# 3-RF.net
KiCad netlist of a schematic drawn in Altium Designer
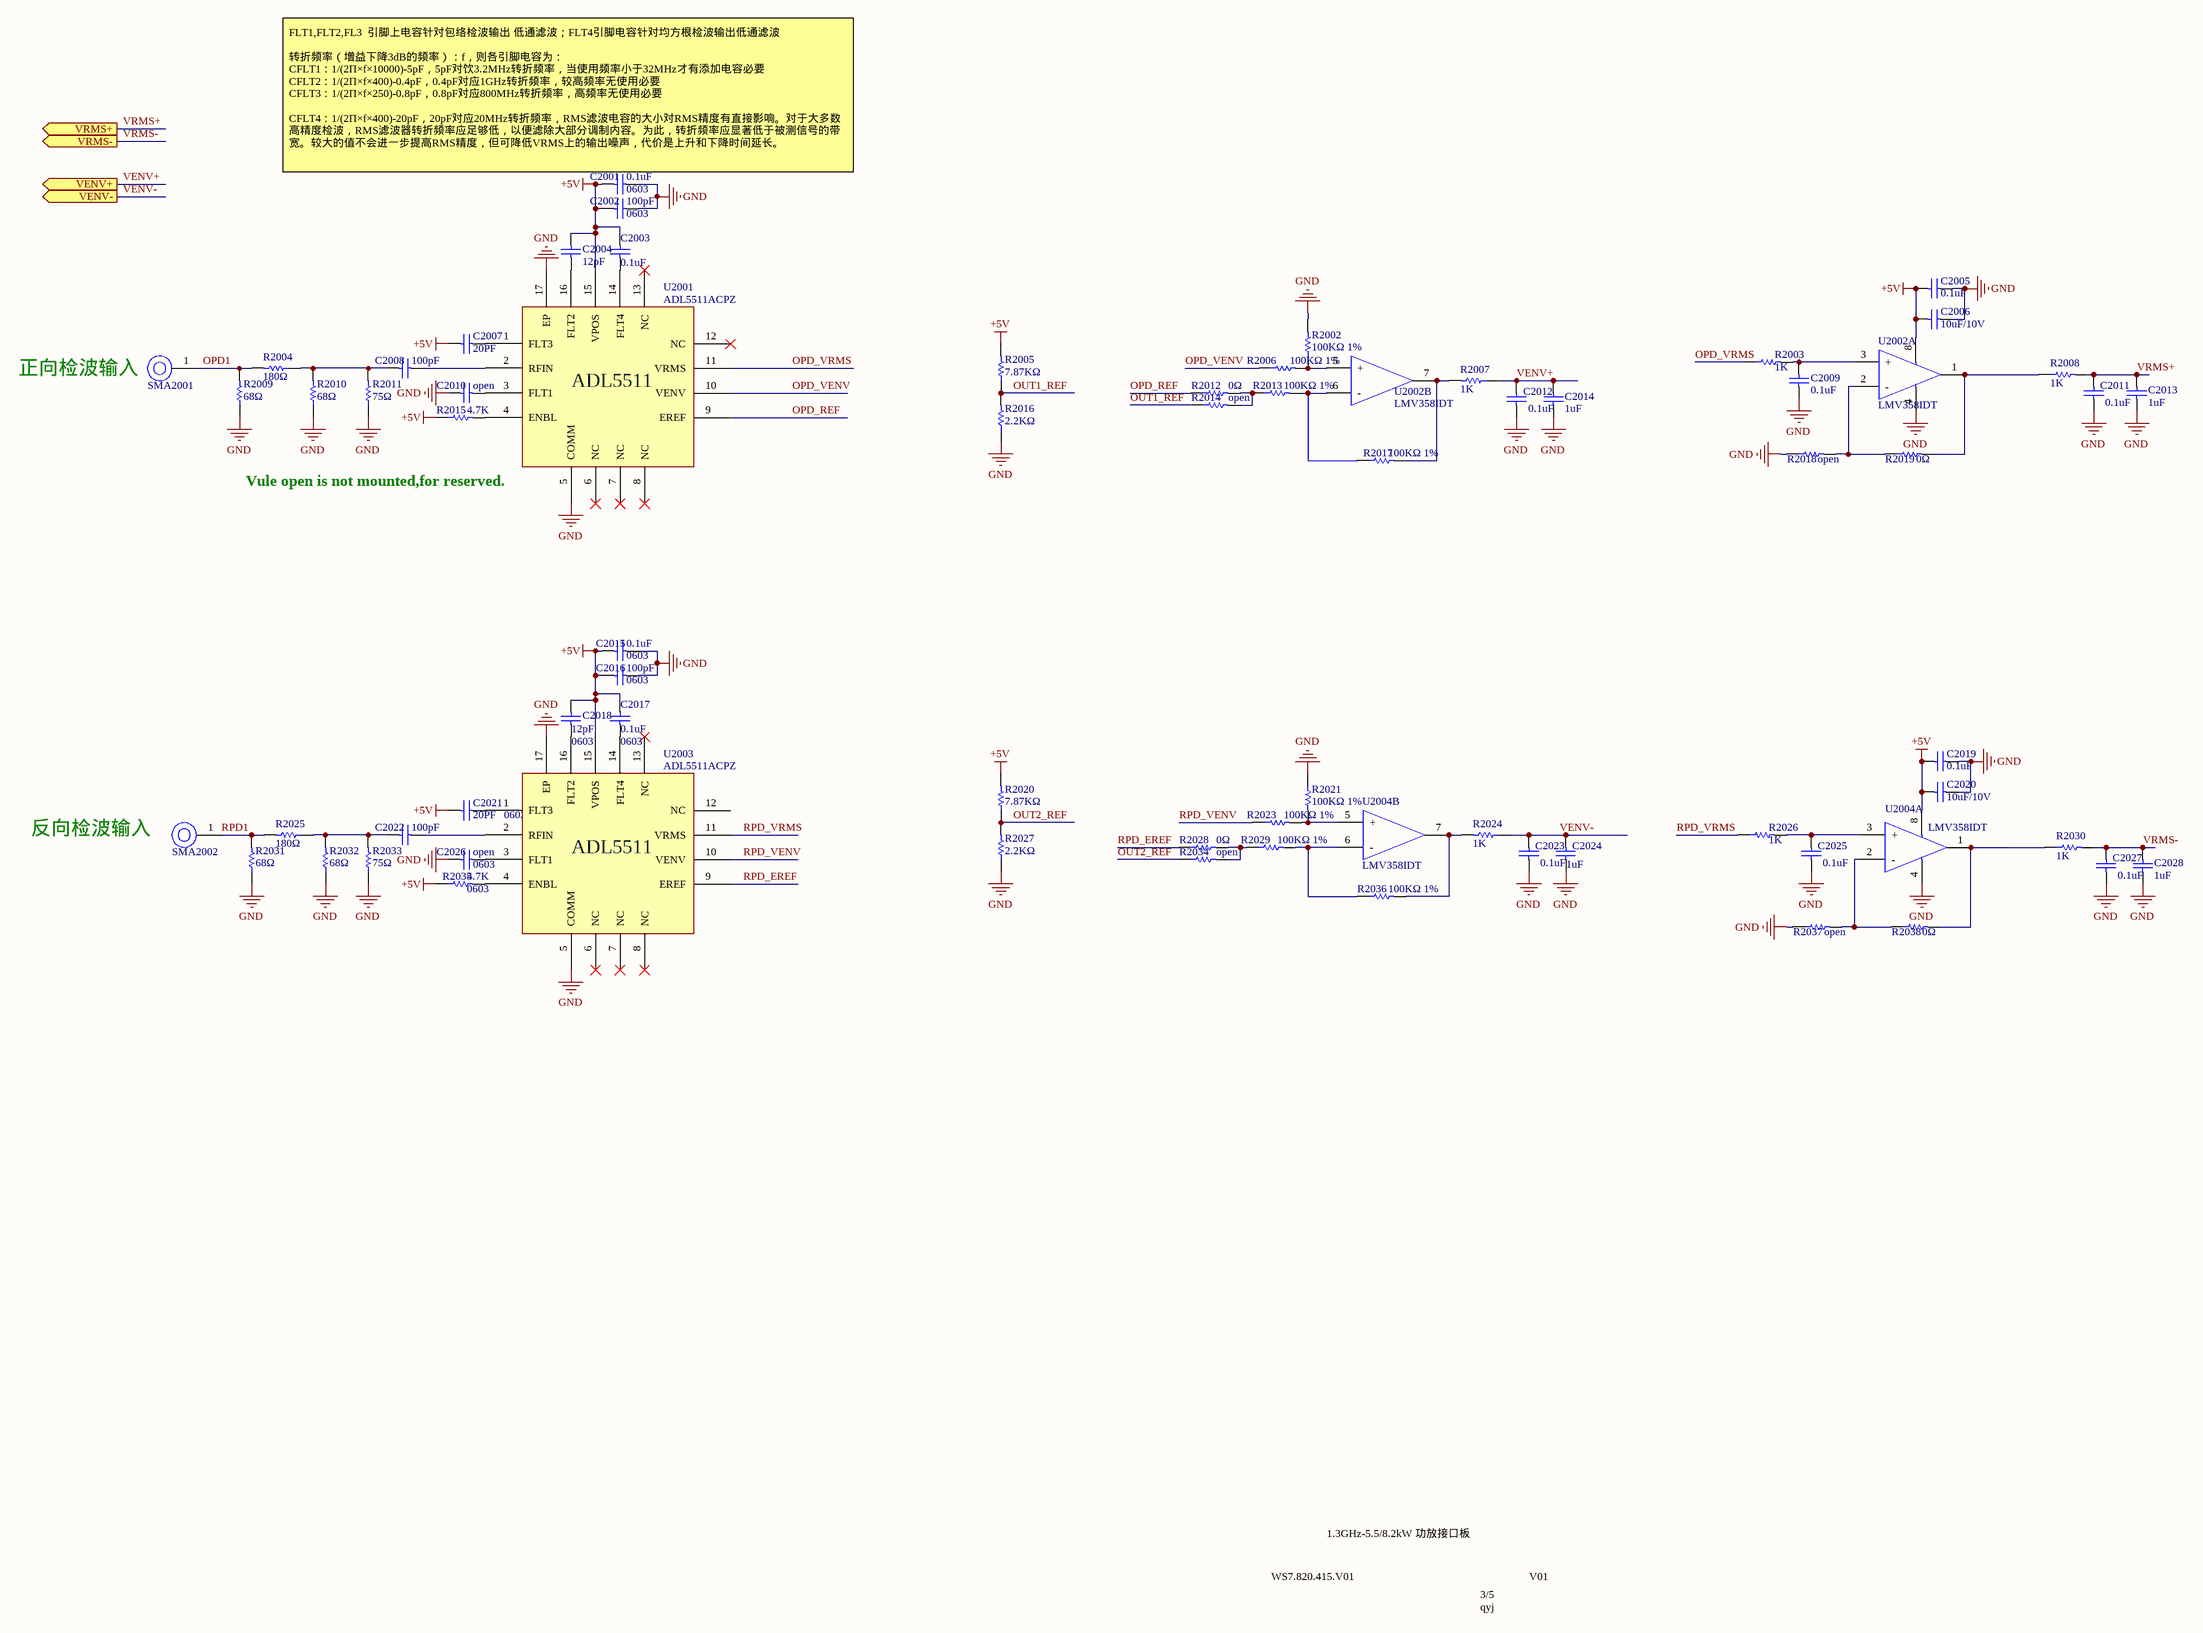
[diagram p0: 3-RF.SchDoc]

(export (version "E")
  (design (tool "Eeschema 10.0.6"))
  (components
    (comp (ref "C2001")
      (value "0.1uF")
      (footprint "C0603")
      (description "贴片电容_GRM188R71H104KA01D_0.1uF±10%,50V,0603")
      (libsource (lib "20贴片电容0603") (part "0.1uF贴片电容"))
    )
    (comp (ref "C2002")
      (value "100pF")
      (footprint "C0603")
      (description "贴片电容_100pF±10%,50V,0603")
      (libsource (lib "20贴片电容0603") (part "1000pF贴片电容"))
    )
    (comp (ref "C2003")
      (value "0.1uF")
      (footprint "C0603")
      (description "贴片电容_GRM188R71H104KA01D_0.1uF±10%,50V,0603")
      (libsource (lib "20贴片电容0603") (part "0.1uF贴片电容"))
    )
    (comp (ref "C2004")
      (value "12pF")
      (footprint "C0603")
      (description "GRM1885C1H390JA01D_39pF±5%,50V,0603")
      (libsource (lib "20贴片电容0603") (part "10pF贴片电容"))
    )
    (comp (ref "C2005")
      (value "0.1uF")
      (footprint "C0603")
      (description "贴片电容_GRM188R71H104KA01D_0.1uF±10%,50V,0603")
      (libsource (lib "20贴片电容0603") (part "0.1uF贴片电容"))
    )
    (comp (ref "C2006")
      (value "10uF/10V")
      (footprint "C0805")
      (description "贴片电容_GRM21BR61A106KE19L_10uF±10%,10V,0805")
      (libsource (lib "21贴片电容0805") (part "10uF贴片电容"))
    )
    (comp (ref "C2007")
      (value "20PF")
      (footprint "C0603")
      (description "贴片电容_GRM1885C1H680JA01D_0603,68PF,50V,±5％,COG")
      (fields (field (name "MPN") "Murata"))
      (libsource (lib "20贴片电容0603") (part "10pF贴片电容"))
    )
    (comp (ref "C2008")
      (value "100pF")
      (footprint "C0805")
      (description "贴片电容_GRM2165C1H101JA01D_100pF±5%,50V,0805")
      (libsource (lib "21贴片电容0805") (part "100pF贴片电容"))
    )
    (comp (ref "C2009")
      (value "0.1uF")
      (footprint "C0603")
      (description "贴片电容_GRM188R71H104KA01D_0.1uF±10%,50V,0603")
      (libsource (lib "20贴片电容0603") (part "0.1uF贴片电容"))
    )
    (comp (ref "C2010")
      (value "open")
      (footprint "C0603")
      (description "贴片电容_GRM188R71H102KA01_1000pF±10%,50V,0603")
      (libsource (lib "20贴片电容0603") (part "1000pF贴片电容"))
    )
    (comp (ref "C2011")
      (value "0.1uF")
      (footprint "C0603")
      (description "贴片电容_GRM188R71H104KA01D_0.1uF±10%,50V,0603")
      (libsource (lib "20贴片电容0603") (part "0.1uF贴片电容"))
    )
    (comp (ref "C2012")
      (value "0.1uF")
      (footprint "C0603")
      (description "贴片电容_GRM188R71H104KA01D_0.1uF±10%,50V,0603")
      (libsource (lib "20贴片电容0603") (part "0.1uF贴片电容"))
    )
    (comp (ref "C2013")
      (value "1uF")
      (footprint "C0603")
      (description "贴片电容_GRM188R60J106ME47D_10uF±20%,6.3V,0603")
      (libsource (lib "20贴片电容0603") (part "10uF贴片电容"))
    )
    (comp (ref "C2014") (value "1uF") (footprint "C0603") (libsource (lib "20贴片电容0603") (part "10uF贴片电容")))
    (comp (ref "C2015")
      (value "0.1uF")
      (footprint "C0603")
      (description "贴片电容_GRM188R71H104KA01D_0.1uF±10%,50V,0603")
      (libsource (lib "20贴片电容0603") (part "0.1uF贴片电容"))
    )
    (comp (ref "C2016")
      (value "100pF")
      (footprint "C0603")
      (description "贴片电容_100pF±10%,50V,0603")
      (libsource (lib "20贴片电容0603") (part "1000pF贴片电容"))
    )
    (comp (ref "C2017")
      (value "0.1uF")
      (footprint "C0603")
      (description "贴片电容_GRM188R71H104KA01D_0.1uF±10%,50V,0603")
      (libsource (lib "20贴片电容0603") (part "0.1uF贴片电容"))
    )
    (comp (ref "C2018")
      (value "12pF")
      (footprint "C0603")
      (description "GRM1885C1H390JA01D_39pF±5%,50V,0603")
      (libsource (lib "20贴片电容0603") (part "10pF贴片电容"))
    )
    (comp (ref "C2019")
      (value "0.1uF")
      (footprint "C0603")
      (description "贴片电容_GRM188R71H104KA01D_0.1uF±10%,50V,0603")
      (libsource (lib "20贴片电容0603") (part "0.1uF贴片电容"))
    )
    (comp (ref "C2020")
      (value "10uF/10V")
      (footprint "C0805")
      (description "贴片电容_GRM21BR61A106KE19L_10uF±10%,10V,0805")
      (libsource (lib "21贴片电容0805") (part "10uF贴片电容"))
    )
    (comp (ref "C2021")
      (value "20PF")
      (footprint "C0603")
      (description "贴片电容_GRM1885C1H680JA01D_0603,68PF,50V,±5％,COG")
      (fields (field (name "MPN") "Murata"))
      (libsource (lib "20贴片电容0603") (part "10pF贴片电容"))
    )
    (comp (ref "C2022")
      (value "100pF")
      (footprint "C0805")
      (description "贴片电容_GRM2165C1H101JA01D_100pF±5%,50V,0805")
      (libsource (lib "21贴片电容0805") (part "100pF贴片电容"))
    )
    (comp (ref "C2023")
      (value "0.1uF")
      (footprint "C0603")
      (description "贴片电容_GRM188R71H104KA01D_0.1uF±10%,50V,0603")
      (libsource (lib "20贴片电容0603") (part "0.1uF贴片电容"))
    )
    (comp (ref "C2024") (value "1uF") (footprint "C0603") (libsource (lib "20贴片电容0603") (part "10uF贴片电容")))
    (comp (ref "C2025")
      (value "0.1uF")
      (footprint "C0603")
      (description "贴片电容_GRM188R71H104KA01D_0.1uF±10%,50V,0603")
      (libsource (lib "20贴片电容0603") (part "0.1uF贴片电容"))
    )
    (comp (ref "C2026")
      (value "open")
      (footprint "C0603")
      (description "贴片电容_GRM188R71H102KA01_1000pF±10%,50V,0603")
      (libsource (lib "20贴片电容0603") (part "1000pF贴片电容"))
    )
    (comp (ref "C2027")
      (value "0.1uF")
      (footprint "C0603")
      (description "贴片电容_GRM188R71H104KA01D_0.1uF±10%,50V,0603")
      (libsource (lib "20贴片电容0603") (part "0.1uF贴片电容"))
    )
    (comp (ref "C2028")
      (value "1uF")
      (footprint "C0603")
      (description "贴片电容_GRM188R60J106ME47D_10uF±20%,6.3V,0603")
      (libsource (lib "20贴片电容0603") (part "10uF贴片电容"))
    )
    (comp (ref "R2002")
      (value "100KΩ 1%")
      (footprint "R0603")
      (libsource (lib "10贴片电阻0603") (part "430Ω贴片电阻"))
    )
    (comp (ref "R2003")
      (value "1K")
      (footprint "R0603")
      (description "贴片电阻_1K±5%,0603")
      (libsource (lib "10贴片电阻0603") (part "1K贴片电阻"))
    )
    (comp (ref "R2004")
      (value "180Ω")
      (footprint "R1206")
      (description "贴片电阻_1206,180Ω,±5％")
      (libsource (lib "12贴片电阻1206") (part "56Ω贴片电阻"))
    )
    (comp (ref "R2005")
      (value "7.87KΩ")
      (footprint "R0603")
      (description "0603,7.87KΩ,±1％")
      (libsource (lib "10贴片电阻0603") (part "0Ω贴片电阻"))
    )
    (comp (ref "R2006")
      (value "100KΩ 1%")
      (footprint "R0603")
      (libsource (lib "10贴片电阻0603") (part "430Ω贴片电阻"))
    )
    (comp (ref "R2007")
      (value "1K")
      (footprint "R0603")
      (description "贴片电阻_1K±5%,0603")
      (libsource (lib "10贴片电阻0603") (part "10K贴片电阻"))
    )
    (comp (ref "R2008")
      (value "1K")
      (footprint "R0603")
      (description "贴片电阻_1K±5%,0603")
      (libsource (lib "10贴片电阻0603") (part "10K贴片电阻"))
    )
    (comp (ref "R2009")
      (value "68Ω")
      (footprint "R1206")
      (description "贴片电阻_68Ω±5%,1206")
      (libsource (lib "12贴片电阻1206") (part "56Ω贴片电阻"))
    )
    (comp (ref "R2010")
      (value "68Ω")
      (footprint "R1206")
      (description "贴片电阻_68Ω±5%,1206")
      (libsource (lib "12贴片电阻1206") (part "56Ω贴片电阻"))
    )
    (comp (ref "R2011")
      (value "75Ω")
      (footprint "R0805")
      (description "贴片电阻_75Ω±5%,0805")
      (libsource (lib "11贴片电阻0805") (part "75Ω贴片电阻"))
    )
    (comp (ref "R2012")
      (value "0Ω")
      (footprint "R0603")
      (description "贴片电阻_0Ω±5%,0603")
      (libsource (lib "10贴片电阻0603") (part "0Ω贴片电阻"))
    )
    (comp (ref "R2013")
      (value "100KΩ 1%")
      (footprint "R0603")
      (libsource (lib "10贴片电阻0603") (part "430Ω贴片电阻"))
    )
    (comp (ref "R2014")
      (value "open")
      (footprint "R0603")
      (description "贴片电阻_0Ω±5%,0603")
      (libsource (lib "10贴片电阻0603") (part "0Ω贴片电阻"))
    )
    (comp (ref "R2015")
      (value "4.7K")
      (footprint "R0603")
      (description "贴片电阻_4.7K±5%,0603")
      (libsource (lib "10贴片电阻0603") (part "4.7K贴片电阻"))
    )
    (comp (ref "R2016")
      (value "2.2KΩ")
      (footprint "R0603")
      (description "0603,2.2KΩ,±1％")
      (libsource (lib "10贴片电阻0603") (part "0Ω贴片电阻"))
    )
    (comp (ref "R2017")
      (value "100KΩ 1%")
      (footprint "R0603")
      (libsource (lib "10贴片电阻0603") (part "430Ω贴片电阻"))
    )
    (comp (ref "R2018") (value "open") (footprint "R0603") (libsource (lib "10贴片电阻0603") (part "0Ω贴片电阻")))
    (comp (ref "R2019")
      (value "0Ω")
      (footprint "R0603")
      (description "贴片电阻_0Ω±5%,0603")
      (libsource (lib "10贴片电阻0603") (part "0Ω贴片电阻"))
    )
    (comp (ref "R2020")
      (value "7.87KΩ")
      (footprint "R0603")
      (description "0603,7.87KΩ,±1％")
      (libsource (lib "10贴片电阻0603") (part "0Ω贴片电阻"))
    )
    (comp (ref "R2021")
      (value "100KΩ 1%")
      (footprint "R0603")
      (libsource (lib "10贴片电阻0603") (part "430Ω贴片电阻"))
    )
    (comp (ref "R2023")
      (value "100KΩ 1%")
      (footprint "R0603")
      (libsource (lib "10贴片电阻0603") (part "430Ω贴片电阻"))
    )
    (comp (ref "R2024")
      (value "1K")
      (footprint "R0603")
      (description "贴片电阻_1K±5%,0603")
      (libsource (lib "10贴片电阻0603") (part "10K贴片电阻"))
    )
    (comp (ref "R2025")
      (value "180Ω")
      (footprint "R1206")
      (description "贴片电阻_1206,180Ω,±5％")
      (libsource (lib "12贴片电阻1206") (part "56Ω贴片电阻"))
    )
    (comp (ref "R2026")
      (value "1K")
      (footprint "R0603")
      (description "贴片电阻_1K±5%,0603")
      (libsource (lib "10贴片电阻0603") (part "1K贴片电阻"))
    )
    (comp (ref "R2027")
      (value "2.2KΩ")
      (footprint "R0603")
      (description "0603,2.2KΩ,±1％")
      (libsource (lib "10贴片电阻0603") (part "0Ω贴片电阻"))
    )
    (comp (ref "R2028")
      (value "0Ω")
      (footprint "R0603")
      (description "贴片电阻_0Ω±5%,0603")
      (libsource (lib "10贴片电阻0603") (part "0Ω贴片电阻"))
    )
    (comp (ref "R2029")
      (value "100KΩ 1%")
      (footprint "R0603")
      (libsource (lib "10贴片电阻0603") (part "430Ω贴片电阻"))
    )
    (comp (ref "R2030")
      (value "1K")
      (footprint "R0603")
      (description "贴片电阻_1K±5%,0603")
      (libsource (lib "10贴片电阻0603") (part "10K贴片电阻"))
    )
    (comp (ref "R2031")
      (value "68Ω")
      (footprint "R1206")
      (description "贴片电阻_68Ω±5%,1206")
      (libsource (lib "12贴片电阻1206") (part "56Ω贴片电阻"))
    )
    (comp (ref "R2032")
      (value "68Ω")
      (footprint "R1206")
      (description "贴片电阻_68Ω±5%,1206")
      (libsource (lib "12贴片电阻1206") (part "56Ω贴片电阻"))
    )
    (comp (ref "R2033")
      (value "75Ω")
      (footprint "R0805")
      (description "贴片电阻_75Ω±5%,0805")
      (libsource (lib "11贴片电阻0805") (part "75Ω贴片电阻"))
    )
    (comp (ref "R2034")
      (value "open")
      (footprint "R0603")
      (description "贴片电阻_0Ω±5%,0603")
      (libsource (lib "10贴片电阻0603") (part "0Ω贴片电阻"))
    )
    (comp (ref "R2035")
      (value "4.7K")
      (footprint "R0603")
      (description "贴片电阻_4.7K±5%,0603")
      (libsource (lib "10贴片电阻0603") (part "4.7K贴片电阻"))
    )
    (comp (ref "R2036")
      (value "100KΩ 1%")
      (footprint "R0603")
      (libsource (lib "10贴片电阻0603") (part "430Ω贴片电阻"))
    )
    (comp (ref "R2037") (value "open") (footprint "R0603") (libsource (lib "10贴片电阻0603") (part "0Ω贴片电阻")))
    (comp (ref "R2038")
      (value "0Ω")
      (footprint "R0603")
      (description "贴片电阻_0Ω±5%,0603")
      (libsource (lib "10贴片电阻0603") (part "0Ω贴片电阻"))
    )
    (comp (ref "SMA2001")
      (value "SMA-KFD-4")
      (footprint "SMA-50KFD-4")
      (description "射频同轴连接器_SMA-KFD-4")
      (libsource (lib "90RF连接器") (part "SMA-50KFD-4"))
    )
    (comp (ref "SMA2002")
      (value "SMA-KFD-4")
      (footprint "SMA-50KFD-4")
      (description "射频同轴连接器_SMA-KFD-4")
      (libsource (lib "90RF连接器") (part "SMA-50KFD-4"))
    )
    (comp (ref "U2001")
      (value "ADL5511ACPZ")
      (footprint "QFN16_0R50_3X3")
      (description "检波器_ADL5511ACPZ_DC~6GHz,LFCSP16")
      (libsource (lib "74检波器") (part "ADL5511ACPZ"))
    )
    (comp (ref "U2002")
      (value "LMV358IDT")
      (footprint "SOIC8_1R27_3R9x4R9")
      (libsource (lib "77运算放大器") (part "OP284"))
    )
    (comp (ref "U2003")
      (value "ADL5511ACPZ")
      (footprint "QFN16_0R50_3X3")
      (description "检波器_ADL5511ACPZ_DC~6GHz,LFCSP16")
      (libsource (lib "74检波器") (part "ADL5511ACPZ"))
    )
    (comp (ref "U2004")
      (value "LMV358IDT")
      (footprint "SOIC8_1R27_3R9x4R9")
      (description "运算放大器_LM358_SOIC8")
      (libsource (lib "77运算放大器") (part "LM358"))
    )
  )
  (nets
    (net (code "1") (name "+5V") (class "Default")
      (node (ref "C2001") (pin "2") (pinfunction "2_2") (pintype "passive"))
      (node (ref "C2002") (pin "1") (pinfunction "1_1") (pintype "passive"))
      (node (ref "C2003") (pin "2") (pinfunction "2_2") (pintype "passive"))
      (node (ref "C2004") (pin "2") (pinfunction "2_2") (pintype "passive"))
      (node (ref "C2005") (pin "1") (pinfunction "1_1") (pintype "passive"))
      (node (ref "C2006") (pin "1") (pinfunction "1_1") (pintype "passive"))
      (node (ref "C2007") (pin "1") (pinfunction "1_1") (pintype "passive"))
      (node (ref "C2015") (pin "2") (pinfunction "2_2") (pintype "passive"))
      (node (ref "C2016") (pin "1") (pinfunction "1_1") (pintype "passive"))
      (node (ref "C2017") (pin "2") (pinfunction "2_2") (pintype "passive"))
      (node (ref "C2018") (pin "2") (pinfunction "2_2") (pintype "passive"))
      (node (ref "C2019") (pin "1") (pinfunction "1_1") (pintype "passive"))
      (node (ref "C2020") (pin "1") (pinfunction "1_1") (pintype "passive"))
      (node (ref "C2021") (pin "1") (pinfunction "1_1") (pintype "passive"))
      (node (ref "R2005") (pin "2") (pinfunction "2_2") (pintype "passive"))
      (node (ref "R2015") (pin "1") (pinfunction "1_1") (pintype "passive"))
      (node (ref "R2020") (pin "2") (pinfunction "2_2") (pintype "passive"))
      (node (ref "R2035") (pin "1") (pinfunction "1_1") (pintype "passive"))
      (node (ref "U2001") (pin "15") (pinfunction "VPOS_15") (pintype "passive"))
      (node (ref "U2002") (pin "8") (pintype "passive"))
      (node (ref "U2003") (pin "15") (pinfunction "VPOS_15") (pintype "passive"))
      (node (ref "U2004") (pin "8") (pintype "passive"))
    )
    (net (code "2") (name "/OPD1") (class "Default")
      (node (ref "R2004") (pin "2") (pinfunction "2_2") (pintype "passive"))
      (node (ref "R2009") (pin "2") (pinfunction "2_2") (pintype "passive"))
      (node (ref "SMA2001") (pin "1") (pinfunction "Sig_1") (pintype "passive"))
    )
    (net (code "3") (name "/OPD_REF") (class "Default")
      (node (ref "R2012") (pin "1") (pinfunction "1_1") (pintype "passive"))
      (node (ref "U2001") (pin "9") (pinfunction "EREF_9") (pintype "passive"))
    )
    (net (code "4") (name "/OPD_VENV") (class "Default")
      (node (ref "R2006") (pin "1") (pinfunction "1_1") (pintype "passive"))
      (node (ref "U2001") (pin "10") (pinfunction "VENV_10") (pintype "passive"))
    )
    (net (code "5") (name "/OPD_VRMS") (class "Default")
      (node (ref "R2003") (pin "1") (pinfunction "1_1") (pintype "passive"))
      (node (ref "U2001") (pin "11") (pinfunction "VRMS_11") (pintype "passive"))
    )
    (net (code "6") (name "/OUT1_REF") (class "Default")
      (node (ref "R2005") (pin "1") (pinfunction "1_1") (pintype "passive"))
      (node (ref "R2014") (pin "1") (pinfunction "1_1") (pintype "passive"))
      (node (ref "R2016") (pin "2") (pinfunction "2_2") (pintype "passive"))
    )
    (net (code "7") (name "/OUT2_REF") (class "Default")
      (node (ref "R2020") (pin "1") (pinfunction "1_1") (pintype "passive"))
      (node (ref "R2027") (pin "2") (pinfunction "2_2") (pintype "passive"))
      (node (ref "R2034") (pin "1") (pinfunction "1_1") (pintype "passive"))
    )
    (net (code "8") (name "/RPD1") (class "Default")
      (node (ref "R2025") (pin "2") (pinfunction "2_2") (pintype "passive"))
      (node (ref "R2031") (pin "2") (pinfunction "2_2") (pintype "passive"))
      (node (ref "SMA2002") (pin "1") (pinfunction "Sig_1") (pintype "passive"))
    )
    (net (code "9") (name "/RPD_EREF") (class "Default")
      (node (ref "R2028") (pin "1") (pinfunction "1_1") (pintype "passive"))
      (node (ref "U2003") (pin "9") (pinfunction "EREF_9") (pintype "passive"))
    )
    (net (code "10") (name "/RPD_VENV") (class "Default")
      (node (ref "R2023") (pin "1") (pinfunction "1_1") (pintype "passive"))
      (node (ref "U2003") (pin "10") (pinfunction "VENV_10") (pintype "passive"))
    )
    (net (code "11") (name "/RPD_VRMS") (class "Default")
      (node (ref "R2026") (pin "1") (pinfunction "1_1") (pintype "passive"))
      (node (ref "U2003") (pin "11") (pinfunction "VRMS_11") (pintype "passive"))
    )
    (net (code "12") (name "/VENV+") (class "Default")
      (node (ref "C2012") (pin "2") (pinfunction "2_2") (pintype "passive"))
      (node (ref "C2014") (pin "2") (pinfunction "2_2") (pintype "passive"))
      (node (ref "R2007") (pin "1") (pinfunction "1_1") (pintype "passive"))
    )
    (net (code "13") (name "/VENV-") (class "Default")
      (node (ref "C2023") (pin "2") (pinfunction "2_2") (pintype "passive"))
      (node (ref "C2024") (pin "2") (pinfunction "2_2") (pintype "passive"))
      (node (ref "R2024") (pin "1") (pinfunction "1_1") (pintype "passive"))
    )
    (net (code "14") (name "/VRMS+") (class "Default")
      (node (ref "C2011") (pin "2") (pinfunction "2_2") (pintype "passive"))
      (node (ref "C2013") (pin "2") (pinfunction "2_2") (pintype "passive"))
      (node (ref "R2008") (pin "2") (pinfunction "2_2") (pintype "passive"))
    )
    (net (code "15") (name "/VRMS-") (class "Default")
      (node (ref "C2027") (pin "2") (pinfunction "2_2") (pintype "passive"))
      (node (ref "C2028") (pin "2") (pinfunction "2_2") (pintype "passive"))
      (node (ref "R2030") (pin "2") (pinfunction "2_2") (pintype "passive"))
    )
    (net (code "16") (name "GND") (class "Default")
      (node (ref "C2001") (pin "1") (pinfunction "1_1") (pintype "passive"))
      (node (ref "C2002") (pin "2") (pinfunction "2_2") (pintype "passive"))
      (node (ref "C2005") (pin "2") (pinfunction "2_2") (pintype "passive"))
      (node (ref "C2006") (pin "2") (pinfunction "2_2") (pintype "passive"))
      (node (ref "C2009") (pin "1") (pinfunction "1_1") (pintype "passive"))
      (node (ref "C2010") (pin "1") (pinfunction "1_1") (pintype "passive"))
      (node (ref "C2011") (pin "1") (pinfunction "1_1") (pintype "passive"))
      (node (ref "C2012") (pin "1") (pinfunction "1_1") (pintype "passive"))
      (node (ref "C2013") (pin "1") (pinfunction "1_1") (pintype "passive"))
      (node (ref "C2014") (pin "1") (pinfunction "1_1") (pintype "passive"))
      (node (ref "C2015") (pin "1") (pinfunction "1_1") (pintype "passive"))
      (node (ref "C2016") (pin "2") (pinfunction "2_2") (pintype "passive"))
      (node (ref "C2019") (pin "2") (pinfunction "2_2") (pintype "passive"))
      (node (ref "C2020") (pin "2") (pinfunction "2_2") (pintype "passive"))
      (node (ref "C2023") (pin "1") (pinfunction "1_1") (pintype "passive"))
      (node (ref "C2024") (pin "1") (pinfunction "1_1") (pintype "passive"))
      (node (ref "C2025") (pin "1") (pinfunction "1_1") (pintype "passive"))
      (node (ref "C2026") (pin "1") (pinfunction "1_1") (pintype "passive"))
      (node (ref "C2027") (pin "1") (pinfunction "1_1") (pintype "passive"))
      (node (ref "C2028") (pin "1") (pinfunction "1_1") (pintype "passive"))
      (node (ref "R2002") (pin "2") (pinfunction "2_2") (pintype "passive"))
      (node (ref "R2009") (pin "1") (pinfunction "1_1") (pintype "passive"))
      (node (ref "R2010") (pin "1") (pinfunction "1_1") (pintype "passive"))
      (node (ref "R2011") (pin "1") (pinfunction "1_1") (pintype "passive"))
      (node (ref "R2016") (pin "1") (pinfunction "1_1") (pintype "passive"))
      (node (ref "R2018") (pin "1") (pinfunction "1_1") (pintype "passive"))
      (node (ref "R2021") (pin "1") (pinfunction "1_1") (pintype "passive"))
      (node (ref "R2027") (pin "1") (pinfunction "1_1") (pintype "passive"))
      (node (ref "R2031") (pin "1") (pinfunction "1_1") (pintype "passive"))
      (node (ref "R2032") (pin "1") (pinfunction "1_1") (pintype "passive"))
      (node (ref "R2033") (pin "1") (pinfunction "1_1") (pintype "passive"))
      (node (ref "R2037") (pin "1") (pinfunction "1_1") (pintype "passive"))
      (node (ref "U2001") (pin "17") (pinfunction "EP_17") (pintype "power_in"))
      (node (ref "U2001") (pin "5") (pinfunction "COMM_5") (pintype "passive"))
      (node (ref "U2002") (pin "4") (pintype "passive"))
      (node (ref "U2003") (pin "17") (pinfunction "EP_17") (pintype "power_in"))
      (node (ref "U2003") (pin "5") (pinfunction "COMM_5") (pintype "passive"))
      (node (ref "U2004") (pin "4") (pintype "passive"))
    )
    (net (code "17") (name "Net-(C2008-Pad1)") (class "Default")
      (node (ref "C2008") (pin "1") (pinfunction "1_1") (pintype "passive"))
      (node (ref "R2004") (pin "1") (pinfunction "1_1") (pintype "passive"))
      (node (ref "R2010") (pin "2") (pinfunction "2_2") (pintype "passive"))
      (node (ref "R2011") (pin "2") (pinfunction "2_2") (pintype "passive"))
    )
    (net (code "18") (name "Net-(C2022-Pad1)") (class "Default")
      (node (ref "C2022") (pin "1") (pinfunction "1_1") (pintype "passive"))
      (node (ref "R2025") (pin "1") (pinfunction "1_1") (pintype "passive"))
      (node (ref "R2032") (pin "2") (pinfunction "2_2") (pintype "passive"))
      (node (ref "R2033") (pin "2") (pinfunction "2_2") (pintype "passive"))
    )
    (net (code "19") (name "Net-(R2007-Pad2)") (class "Default")
      (node (ref "R2007") (pin "2") (pinfunction "2_2") (pintype "passive"))
      (node (ref "R2017") (pin "2") (pinfunction "2_2") (pintype "passive"))
      (node (ref "U2002") (pin "7") (pintype "passive"))
    )
    (net (code "20") (name "Net-(R2008-Pad1)") (class "Default")
      (node (ref "R2008") (pin "1") (pinfunction "1_1") (pintype "passive"))
      (node (ref "R2019") (pin "2") (pinfunction "2_2") (pintype "passive"))
      (node (ref "U2002") (pin "1") (pintype "passive"))
    )
    (net (code "21") (name "Net-(R2012-Pad2)") (class "Default")
      (node (ref "R2012") (pin "2") (pinfunction "2_2") (pintype "passive"))
      (node (ref "R2013") (pin "1") (pinfunction "1_1") (pintype "passive"))
      (node (ref "R2014") (pin "2") (pinfunction "2_2") (pintype "passive"))
    )
    (net (code "22") (name "Net-(R2024-Pad2)") (class "Default")
      (node (ref "R2024") (pin "2") (pinfunction "2_2") (pintype "passive"))
      (node (ref "R2036") (pin "2") (pinfunction "2_2") (pintype "passive"))
      (node (ref "U2004") (pin "7") (pintype "passive"))
    )
    (net (code "23") (name "Net-(R2028-Pad2)") (class "Default")
      (node (ref "R2028") (pin "2") (pinfunction "2_2") (pintype "passive"))
      (node (ref "R2029") (pin "1") (pinfunction "1_1") (pintype "passive"))
      (node (ref "R2034") (pin "2") (pinfunction "2_2") (pintype "passive"))
    )
    (net (code "24") (name "Net-(R2030-Pad1)") (class "Default")
      (node (ref "R2030") (pin "1") (pinfunction "1_1") (pintype "passive"))
      (node (ref "R2038") (pin "2") (pinfunction "2_2") (pintype "passive"))
      (node (ref "U2004") (pin "1") (pintype "passive"))
    )
    (net (code "25") (name "Net-(U2001-ENBL)") (class "Default")
      (node (ref "R2015") (pin "2") (pinfunction "2_2") (pintype "passive"))
      (node (ref "U2001") (pin "4") (pinfunction "ENBL_4") (pintype "passive"))
    )
    (net (code "26") (name "Net-(U2001-FLT1)") (class "Default")
      (node (ref "C2010") (pin "2") (pinfunction "2_2") (pintype "passive"))
      (node (ref "U2001") (pin "3") (pinfunction "FLT1_3") (pintype "passive"))
    )
    (net (code "27") (name "Net-(U2001-FLT2)") (class "Default")
      (node (ref "C2004") (pin "1") (pinfunction "1_1") (pintype "passive"))
      (node (ref "U2001") (pin "16") (pinfunction "FLT2_16") (pintype "passive"))
    )
    (net (code "28") (name "Net-(U2001-FLT3)") (class "Default")
      (node (ref "C2007") (pin "2") (pinfunction "2_2") (pintype "passive"))
      (node (ref "U2001") (pin "1") (pinfunction "FLT3_1") (pintype "passive"))
    )
    (net (code "29") (name "Net-(U2001-FLT4)") (class "Default")
      (node (ref "C2003") (pin "1") (pinfunction "1_1") (pintype "passive"))
      (node (ref "U2001") (pin "14") (pinfunction "FLT4_14") (pintype "passive"))
    )
    (net (code "30") (name "Net-(U2001-RFIN)") (class "Default")
      (node (ref "C2008") (pin "2") (pinfunction "2_2") (pintype "passive"))
      (node (ref "U2001") (pin "2") (pinfunction "RFIN_2") (pintype "passive"))
    )
    (net (code "31") (name "Net-(U2002A-+)") (class "Default")
      (node (ref "C2009") (pin "2") (pinfunction "2_2") (pintype "passive"))
      (node (ref "R2003") (pin "2") (pinfunction "2_2") (pintype "passive"))
      (node (ref "U2002") (pin "3") (pinfunction "+_3") (pintype "passive"))
    )
    (net (code "32") (name "Net-(U2002A--)") (class "Default")
      (node (ref "R2018") (pin "2") (pinfunction "2_2") (pintype "passive"))
      (node (ref "R2019") (pin "1") (pinfunction "1_1") (pintype "passive"))
      (node (ref "U2002") (pin "2") (pinfunction "-_2") (pintype "passive"))
    )
    (net (code "33") (name "Net-(U2002B-+)") (class "Default")
      (node (ref "R2002") (pin "1") (pinfunction "1_1") (pintype "passive"))
      (node (ref "R2006") (pin "2") (pinfunction "2_2") (pintype "passive"))
      (node (ref "U2002") (pin "5") (pinfunction "+_5") (pintype "passive"))
    )
    (net (code "34") (name "Net-(U2002B--)") (class "Default")
      (node (ref "R2013") (pin "2") (pinfunction "2_2") (pintype "passive"))
      (node (ref "R2017") (pin "1") (pinfunction "1_1") (pintype "passive"))
      (node (ref "U2002") (pin "6") (pinfunction "-_6") (pintype "passive"))
    )
    (net (code "35") (name "Net-(U2003-ENBL)") (class "Default")
      (node (ref "R2035") (pin "2") (pinfunction "2_2") (pintype "passive"))
      (node (ref "U2003") (pin "4") (pinfunction "ENBL_4") (pintype "passive"))
    )
    (net (code "36") (name "Net-(U2003-FLT1)") (class "Default")
      (node (ref "C2026") (pin "2") (pinfunction "2_2") (pintype "passive"))
      (node (ref "U2003") (pin "3") (pinfunction "FLT1_3") (pintype "passive"))
    )
    (net (code "37") (name "Net-(U2003-FLT2)") (class "Default")
      (node (ref "C2018") (pin "1") (pinfunction "1_1") (pintype "passive"))
      (node (ref "U2003") (pin "16") (pinfunction "FLT2_16") (pintype "passive"))
    )
    (net (code "38") (name "Net-(U2003-FLT3)") (class "Default")
      (node (ref "C2021") (pin "2") (pinfunction "2_2") (pintype "passive"))
      (node (ref "U2003") (pin "1") (pinfunction "FLT3_1") (pintype "passive"))
    )
    (net (code "39") (name "Net-(U2003-FLT4)") (class "Default")
      (node (ref "C2017") (pin "1") (pinfunction "1_1") (pintype "passive"))
      (node (ref "U2003") (pin "14") (pinfunction "FLT4_14") (pintype "passive"))
    )
    (net (code "40") (name "Net-(U2003-RFIN)") (class "Default")
      (node (ref "C2022") (pin "2") (pinfunction "2_2") (pintype "passive"))
      (node (ref "U2003") (pin "2") (pinfunction "RFIN_2") (pintype "passive"))
    )
    (net (code "41") (name "Net-(U2004A-+)") (class "Default")
      (node (ref "C2025") (pin "2") (pinfunction "2_2") (pintype "passive"))
      (node (ref "R2026") (pin "2") (pinfunction "2_2") (pintype "passive"))
      (node (ref "U2004") (pin "3") (pinfunction "+_3") (pintype "passive"))
    )
    (net (code "42") (name "Net-(U2004A--)") (class "Default")
      (node (ref "R2037") (pin "2") (pinfunction "2_2") (pintype "passive"))
      (node (ref "R2038") (pin "1") (pinfunction "1_1") (pintype "passive"))
      (node (ref "U2004") (pin "2") (pinfunction "-_2") (pintype "passive"))
    )
    (net (code "43") (name "Net-(U2004B-+)") (class "Default")
      (node (ref "R2021") (pin "2") (pinfunction "2_2") (pintype "passive"))
      (node (ref "R2023") (pin "2") (pinfunction "2_2") (pintype "passive"))
      (node (ref "U2004") (pin "5") (pinfunction "+_5") (pintype "passive"))
    )
    (net (code "44") (name "Net-(U2004B--)") (class "Default")
      (node (ref "R2029") (pin "2") (pinfunction "2_2") (pintype "passive"))
      (node (ref "R2036") (pin "1") (pinfunction "1_1") (pintype "passive"))
      (node (ref "U2004") (pin "6") (pinfunction "-_6") (pintype "passive"))
    )
    (net (code "45") (name "unconnected-(U2001-NC-Pad6)") (class "Default")
      (node (ref "U2001") (pin "6") (pinfunction "NC_6") (pintype "passive+no_connect"))
    )
    (net (code "46") (name "unconnected-(U2001-NC-Pad7)") (class "Default")
      (node (ref "U2001") (pin "7") (pinfunction "NC_7") (pintype "passive+no_connect"))
    )
    (net (code "47") (name "unconnected-(U2001-NC-Pad8)") (class "Default")
      (node (ref "U2001") (pin "8") (pinfunction "NC_8") (pintype "passive+no_connect"))
    )
    (net (code "48") (name "unconnected-(U2001-NC-Pad12)") (class "Default")
      (node (ref "U2001") (pin "12") (pinfunction "NC_12") (pintype "passive+no_connect"))
    )
    (net (code "49") (name "unconnected-(U2001-NC-Pad13)") (class "Default")
      (node (ref "U2001") (pin "13") (pinfunction "NC_13") (pintype "passive+no_connect"))
    )
    (net (code "50") (name "unconnected-(U2003-NC-Pad6)") (class "Default")
      (node (ref "U2003") (pin "6") (pinfunction "NC_6") (pintype "passive+no_connect"))
    )
    (net (code "51") (name "unconnected-(U2003-NC-Pad7)") (class "Default")
      (node (ref "U2003") (pin "7") (pinfunction "NC_7") (pintype "passive+no_connect"))
    )
    (net (code "52") (name "unconnected-(U2003-NC-Pad8)") (class "Default")
      (node (ref "U2003") (pin "8") (pinfunction "NC_8") (pintype "passive+no_connect"))
    )
    (net (code "53") (name "unconnected-(U2003-NC-Pad12)") (class "Default")
      (node (ref "U2003") (pin "12") (pinfunction "NC_12") (pintype "passive"))
    )
    (net (code "54") (name "unconnected-(U2003-NC-Pad13)") (class "Default")
      (node (ref "U2003") (pin "13") (pinfunction "NC_13") (pintype "passive+no_connect"))
    )
  )
)
